# pir-sensors-with-esp.net
KiCad netlist of a schematic drawn in EAGLE
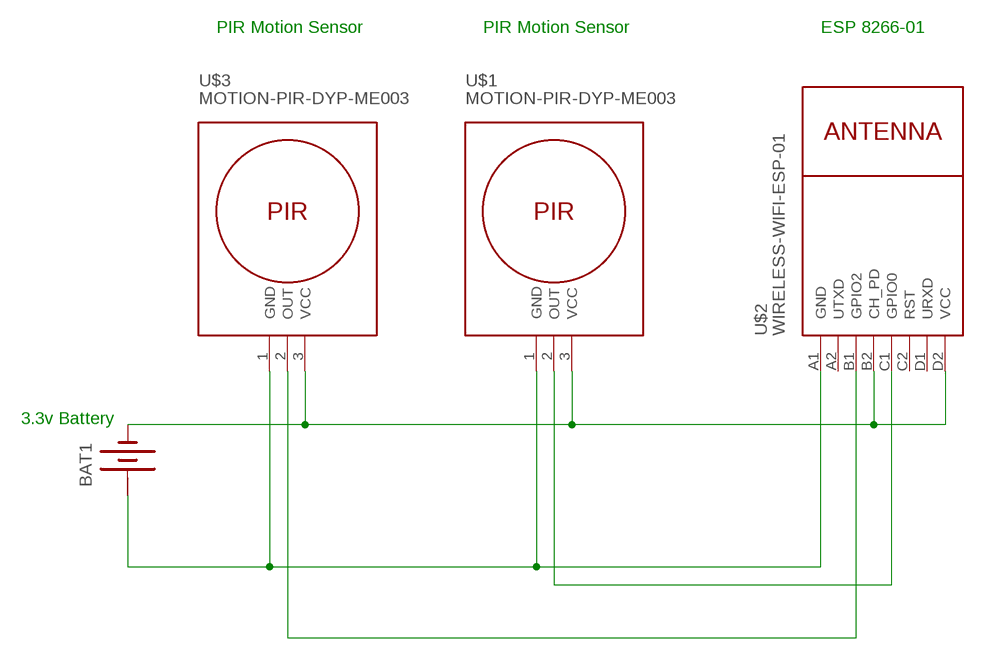
[diagram p0: schematic, sheet 1]

(export (version "E")
  (design (tool "Eeschema 10.0.6"))
  (components
    (comp (ref "BAT1")
      (value "BATTERY")
      (footprint "eagle-import:BATTERY")
      (libsource (lib "eagle-import") (part "BATTERY"))
    )
    (comp (ref "U$1")
      (value "MOTION-PIR-DYP-ME003")
      (footprint "eagle-import:MOTION-PIR-DYP-ME003")
      (libsource (lib "eagle-import") (part "MOTION-PIR-DYP-ME003"))
    )
    (comp (ref "U$2")
      (value "WIRELESS-WIFI-ESP-01")
      (footprint "eagle-import:WIRELESS-WIFI-ESP-01")
      (libsource (lib "eagle-import") (part "WIRELESS-WIFI-ESP-01"))
    )
    (comp (ref "U$3")
      (value "MOTION-PIR-DYP-ME003")
      (footprint "eagle-import:MOTION-PIR-DYP-ME003")
      (libsource (lib "eagle-import") (part "MOTION-PIR-DYP-ME003"))
    )
  )
  (nets
    (net (code "1") (name "/+") (class "Default")
      (node (ref "BAT1") (pin "+@1") (pinfunction "+_+@1") (pintype "power_in"))
    )
    (net (code "2") (name "Net-(U$1-GND)") (class "Default")
      (node (ref "BAT1") (pin "+") (pinfunction "+_+") (pintype "power_in"))
      (node (ref "U$1") (pin "1") (pinfunction "GND_1") (pintype "power_in"))
      (node (ref "U$2") (pin "A1") (pinfunction "GND_A1") (pintype "power_in"))
      (node (ref "U$3") (pin "1") (pinfunction "GND_1") (pintype "power_in"))
    )
    (net (code "3") (name "Net-(U$1-OUT)") (class "Default")
      (node (ref "U$1") (pin "2") (pinfunction "OUT_2") (pintype "output"))
      (node (ref "U$2") (pin "C1") (pinfunction "GPIO0_C1") (pintype "bidirectional"))
    )
    (net (code "4") (name "Net-(U$1-VCC)") (class "Default")
      (node (ref "BAT1") (pin "-") (pinfunction "-_-") (pintype "power_in"))
      (node (ref "U$1") (pin "3") (pinfunction "VCC_3") (pintype "power_in"))
      (node (ref "U$2") (pin "B2") (pinfunction "CH_PD_B2") (pintype "bidirectional"))
      (node (ref "U$2") (pin "D2") (pinfunction "VCC_D2") (pintype "power_in"))
      (node (ref "U$3") (pin "3") (pinfunction "VCC_3") (pintype "power_in"))
    )
    (net (code "5") (name "Net-(U$2-GPIO2)") (class "Default")
      (node (ref "U$2") (pin "B1") (pinfunction "GPIO2_B1") (pintype "bidirectional"))
      (node (ref "U$3") (pin "2") (pinfunction "OUT_2") (pintype "output"))
    )
    (net (code "6") (name "unconnected-(U$2-RST-PadC2)") (class "Default")
      (node (ref "U$2") (pin "C2") (pinfunction "RST_C2") (pintype "bidirectional"))
    )
    (net (code "7") (name "unconnected-(U$2-URXD-PadD1)") (class "Default")
      (node (ref "U$2") (pin "D1") (pinfunction "URXD_D1") (pintype "bidirectional"))
    )
    (net (code "8") (name "unconnected-(U$2-UTXD-PadA2)") (class "Default")
      (node (ref "U$2") (pin "A2") (pinfunction "UTXD_A2") (pintype "bidirectional"))
    )
  )
)
